# FMB-USB.net
KiCad netlist of a schematic drawn in Altium Designer
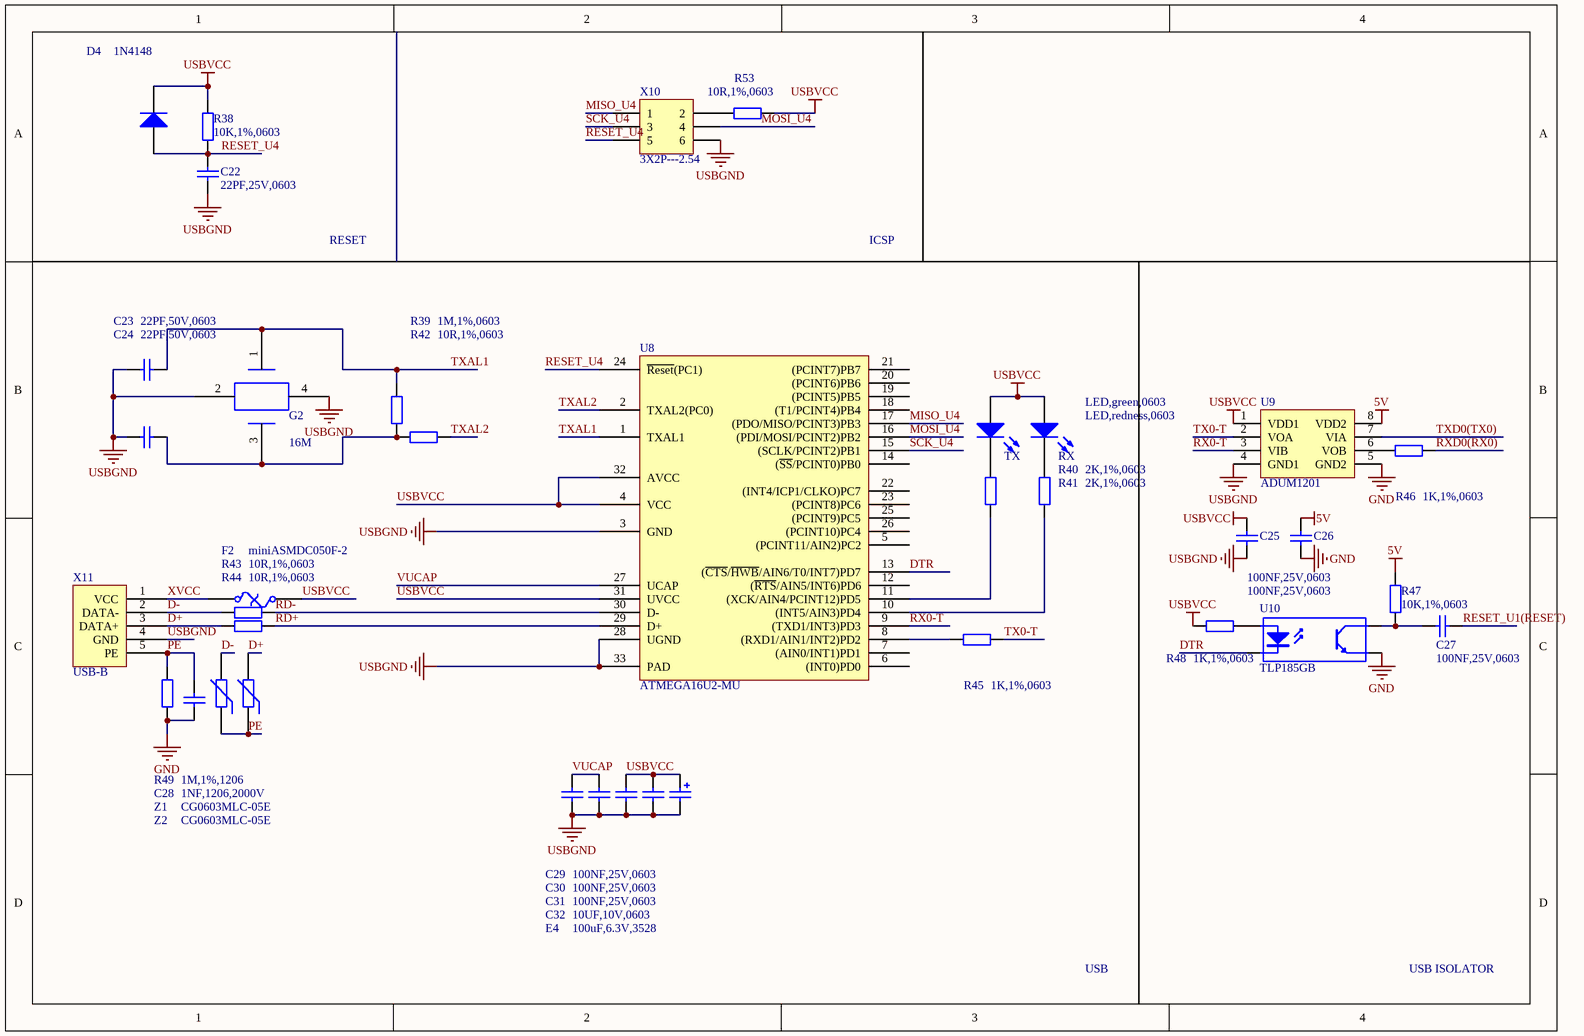
[diagram p0: FMB-USB.SchDoc]

(export (version "E")
  (design (tool "Eeschema 10.0.6"))
  (components
    (comp (ref "C22")
      (value "22PF,25V,0603")
      (footprint "RC0603")
      (description "Capacitor")
      (fields (field (name "PUBLISHER") "Altium Limited"))
      (libsource (lib "Miscellaneous Devices") (part "Cap"))
    )
    (comp (ref "C23")
      (value "22PF,50V,0603")
      (footprint "RC0603")
      (description "Capacitor")
      (fields (field (name "PUBLISHER") "Altium Limited"))
      (libsource (lib "Miscellaneous Devices") (part "Cap"))
    )
    (comp (ref "C24")
      (value "22PF,50V,0603")
      (footprint "RC0603")
      (description "Capacitor")
      (fields (field (name "PUBLISHER") "Altium Limited"))
      (libsource (lib "Miscellaneous Devices") (part "Cap"))
    )
    (comp (ref "C25")
      (value "100NF,25V,0603")
      (footprint "RC0603")
      (description "Capacitor")
      (fields (field (name "PUBLISHER") "Altium Limited"))
      (libsource (lib "Miscellaneous Devices") (part "Cap"))
    )
    (comp (ref "C26")
      (value "100NF,25V,0603")
      (footprint "RC0603")
      (description "Capacitor")
      (fields (field (name "PUBLISHER") "Altium Limited"))
      (libsource (lib "Miscellaneous Devices") (part "Cap"))
    )
    (comp (ref "C27")
      (value "100NF,25V,0603")
      (footprint "RC0603")
      (description "Capacitor")
      (fields (field (name "PUBLISHER") "Altium Limited"))
      (libsource (lib "Miscellaneous Devices") (part "Cap"))
    )
    (comp (ref "C28")
      (value "1NF,1206,2000V")
      (footprint "RC1206")
      (description "Capacitor")
      (fields (field (name "PUBLISHER") "Altium Limited"))
      (libsource (lib "Miscellaneous Devices") (part "Cap"))
    )
    (comp (ref "C29")
      (value "100NF,25V,0603")
      (footprint "RC0603")
      (description "Capacitor")
      (fields (field (name "PUBLISHER") "Altium Limited"))
      (libsource (lib "Miscellaneous Devices") (part "Cap"))
    )
    (comp (ref "C30")
      (value "100NF,25V,0603")
      (footprint "RC0603")
      (description "Capacitor")
      (fields (field (name "PUBLISHER") "Altium Limited"))
      (libsource (lib "Miscellaneous Devices") (part "Cap"))
    )
    (comp (ref "C31")
      (value "100NF,25V,0603")
      (footprint "RC0603")
      (description "Capacitor")
      (fields (field (name "PUBLISHER") "Altium Limited"))
      (libsource (lib "Miscellaneous Devices") (part "Cap"))
    )
    (comp (ref "C32")
      (value "10UF,10V,0603")
      (footprint "RC0603")
      (description "Capacitor")
      (fields (field (name "PUBLISHER") "Altium Limited"))
      (libsource (lib "Miscellaneous Devices") (part "Cap"))
    )
    (comp (ref "D4")
      (value "1N4148")
      (footprint "SOD-323")
      (description "Default Diode")
      (fields (field (name "PUBLISHER") "Altium Limited"))
      (libsource (lib "Miscellaneous Devices") (part "Diode"))
    )
    (comp (ref "E4")
      (value "100uF,6.3V,3528")
      (footprint "3528-21")
      (description "Polarized Capacitor (Axial)")
      (fields (field (name "PUBLISHER") "Altium Limited"))
      (libsource (lib "Miscellaneous Devices") (part "Cap Pol2"))
    )
    (comp (ref "F2")
      (value "miniASMDC050F-2")
      (footprint "RC1812")
      (description "Thermal Fuse")
      (fields (field (name "PUBLISHER") "Altium Limited"))
      (libsource (lib "Miscellaneous Devices") (part "Fuse Thermal"))
    )
    (comp (ref "G2") (value "16M") (footprint "Y-3225") (libsource (lib "STM32F407VE") (part "G")))
    (comp (ref "R38")
      (value "10K,1%,0603")
      (footprint "RC0603")
      (description "Resistor")
      (fields (field (name "PUBLISHER") "Altium Limited"))
      (libsource (lib "") (part "Res2_1"))
    )
    (comp (ref "R39")
      (value "1M,1%,0603")
      (footprint "RC0603")
      (description "Resistor")
      (fields (field (name "PUBLISHER") "Altium Limited"))
      (libsource (lib "") (part "Res2_1"))
    )
    (comp (ref "R40")
      (value "2K,1%,0603")
      (footprint "RC0603")
      (description "Resistor")
      (fields (field (name "PUBLISHER") "Altium Limited"))
      (libsource (lib "") (part "Res2_1"))
    )
    (comp (ref "R41")
      (value "2K,1%,0603")
      (footprint "RC0603")
      (description "Resistor")
      (fields (field (name "PUBLISHER") "Altium Limited"))
      (libsource (lib "") (part "Res2_1"))
    )
    (comp (ref "R42")
      (value "10R,1%,0603")
      (footprint "RC0603")
      (description "Resistor")
      (fields (field (name "PUBLISHER") "Altium Limited"))
      (libsource (lib "Miscellaneous Devices") (part "Res2"))
    )
    (comp (ref "R43")
      (value "10R,1%,0603")
      (footprint "RC0603")
      (description "Resistor")
      (fields (field (name "PUBLISHER") "Altium Limited"))
      (libsource (lib "Miscellaneous Devices") (part "Res2"))
    )
    (comp (ref "R44")
      (value "10R,1%,0603")
      (footprint "RC0603")
      (description "Resistor")
      (fields (field (name "PUBLISHER") "Altium Limited"))
      (libsource (lib "Miscellaneous Devices") (part "Res2"))
    )
    (comp (ref "R45")
      (value "1K,1%,0603")
      (footprint "RC0603")
      (description "Resistor")
      (fields (field (name "PUBLISHER") "Altium Limited"))
      (libsource (lib "") (part "Res2_3"))
    )
    (comp (ref "R46")
      (value "1K,1%,0603")
      (footprint "RC0603")
      (description "Resistor")
      (fields (field (name "PUBLISHER") "Altium Limited"))
      (libsource (lib "") (part "Res2_3"))
    )
    (comp (ref "R47")
      (value "10K,1%,0603")
      (footprint "RC0603")
      (description "Resistor")
      (fields (field (name "PUBLISHER") "Altium Limited"))
      (libsource (lib "") (part "Res2_2"))
    )
    (comp (ref "R48")
      (value "1K,1%,0603")
      (footprint "RC0603")
      (description "Resistor")
      (fields (field (name "PUBLISHER") "Altium Limited"))
      (libsource (lib "Miscellaneous Devices") (part "Res2"))
    )
    (comp (ref "R49")
      (value "1M,1%,1206")
      (footprint "RC1206")
      (description "Resistor")
      (fields (field (name "PUBLISHER") "Altium Limited"))
      (libsource (lib "") (part "Res2_2"))
    )
    (comp (ref "R53")
      (value "10R,1%,0603")
      (footprint "RC0603")
      (description "Resistor")
      (fields (field (name "PUBLISHER") "Altium Limited"))
      (libsource (lib "") (part "Res2_3"))
    )
    (comp (ref "RX")
      (value "LED,redness,0603")
      (footprint "LED-0603")
      (description "Typical INFRARED GaAs LED")
      (fields (field (name "PUBLISHER") "Altium Limited"))
      (libsource (lib "Miscellaneous Devices") (part "LED0"))
    )
    (comp (ref "TX")
      (value "LED,green,0603")
      (footprint "LED-0603")
      (description "Typical INFRARED GaAs LED")
      (fields (field (name "PUBLISHER") "Altium Limited"))
      (libsource (lib "Miscellaneous Devices") (part "LED0"))
    )
    (comp (ref "U8")
      (value "ATMEGA16U2-MU")
      (footprint "QFN-32")
      (libsource (lib "LDO原理图库") (part "ATMEGA8U2-MU"))
    )
    (comp (ref "U9") (value "ADUM1201") (footprint "SO-8N") (libsource (lib "ADUM1201") (part "ADUM1201")))
    (comp (ref "U10")
      (value "TLP185GB")
      (footprint "SO-4")
      (description "4-Pin Phototransistor Optocoupler")
      (fields (field (name "PUBLISHER") "Altium Limited"))
      (libsource (lib "Miscellaneous Devices") (part "Optoisolator1"))
    )
    (comp (ref "X10")
      (value "3X2P---2.54")
      (footprint "HDR2X3")
      (description "Header, 3-Pin, Dual row")
      (fields (field (name "PUBLISHER") "Altium Limited"))
      (libsource (lib "Miscellaneous Connectors") (part "Header 3X2"))
    )
    (comp (ref "X11") (value "USB-B") (footprint "USB-B180") (libsource (lib "LDO原理图库") (part "B-USC")))
    (comp (ref "Z1")
      (value "CG0603MLC-05E")
      (footprint "RC0603")
      (description "Varistor (Voltage-Sensitive Resistor)")
      (fields (field (name "PUBLISHER") "Altium Limited"))
      (libsource (lib "Miscellaneous Devices") (part "Res Varistor"))
    )
    (comp (ref "Z2")
      (value "CG0603MLC-05E")
      (footprint "RC0603")
      (description "Varistor (Voltage-Sensitive Resistor)")
      (fields (field (name "PUBLISHER") "Altium Limited"))
      (libsource (lib "Miscellaneous Devices") (part "Res Varistor"))
    )
  )
  (nets
    (net (code "1") (name "/D+") (class "Default")
      (node (ref "R44") (pin "1") (pinfunction "1_1") (pintype "passive"))
      (node (ref "X11") (pin "3") (pinfunction "DATA+_3") (pintype "passive"))
      (node (ref "Z2") (pin "2") (pinfunction "2_2") (pintype "passive"))
    )
    (net (code "2") (name "/D-") (class "Default")
      (node (ref "R43") (pin "1") (pinfunction "1_1") (pintype "passive"))
      (node (ref "X11") (pin "2") (pinfunction "DATA-_2") (pintype "passive"))
      (node (ref "Z1") (pin "2") (pinfunction "2_2") (pintype "passive"))
    )
    (net (code "3") (name "/DTR") (class "Default")
      (node (ref "U10") (pin "2") (pinfunction "K_2") (pintype "passive"))
      (node (ref "U8") (pin "13") (pinfunction "(~{CTS}/~{HWB}/AIN6/T0/INT7)PD7_13") (pintype "passive"))
    )
    (net (code "4") (name "/MISO_U4") (class "Default")
      (node (ref "U8") (pin "17") (pinfunction "(PDO/MISO/PCINT3)PB3_17") (pintype "passive"))
      (node (ref "X10") (pin "1") (pinfunction "1_1") (pintype "passive"))
    )
    (net (code "5") (name "/MOSI_U4") (class "Default")
      (node (ref "U8") (pin "16") (pinfunction "(PDI/MOSI/PCINT2)PB2_16") (pintype "passive"))
      (node (ref "X10") (pin "4") (pinfunction "4_4") (pintype "passive"))
    )
    (net (code "6") (name "/PE") (class "Default")
      (node (ref "C28") (pin "2") (pinfunction "2_2") (pintype "passive"))
      (node (ref "R49") (pin "2") (pinfunction "2_2") (pintype "passive"))
      (node (ref "X11") (pin "5") (pinfunction "PE_5") (pintype "passive"))
      (node (ref "Z1") (pin "1") (pinfunction "1_1") (pintype "passive"))
      (node (ref "Z2") (pin "1") (pinfunction "1_1") (pintype "passive"))
    )
    (net (code "7") (name "/RD+") (class "Default")
      (node (ref "R44") (pin "2") (pinfunction "2_2") (pintype "passive"))
      (node (ref "U8") (pin "29") (pinfunction "D+_29") (pintype "passive"))
    )
    (net (code "8") (name "/RD-") (class "Default")
      (node (ref "R43") (pin "2") (pinfunction "2_2") (pintype "passive"))
      (node (ref "U8") (pin "30") (pinfunction "D-_30") (pintype "passive"))
    )
    (net (code "9") (name "/RESET_U1(RESET)") (class "Default")
      (node (ref "C27") (pin "1") (pinfunction "1_1") (pintype "passive"))
    )
    (net (code "10") (name "/RESET_U4") (class "Default")
      (node (ref "C22") (pin "1") (pinfunction "1_1") (pintype "passive"))
      (node (ref "D4") (pin "1") (pinfunction "A_1") (pintype "passive"))
      (node (ref "R38") (pin "2") (pinfunction "2_2") (pintype "passive"))
      (node (ref "U8") (pin "24") (pinfunction "~{Reset}(PC1)_24") (pintype "passive"))
      (node (ref "X10") (pin "5") (pinfunction "5_5") (pintype "passive"))
    )
    (net (code "11") (name "/RX0-T") (class "Default")
      (node (ref "U8") (pin "9") (pinfunction "(TXD1/INT3)PD3_9") (pintype "passive"))
      (node (ref "U9") (pin "3") (pinfunction "VIB_3") (pintype "passive"))
    )
    (net (code "12") (name "/RXD0(RX0)") (class "Default")
      (node (ref "R46") (pin "1") (pinfunction "1_1") (pintype "passive"))
    )
    (net (code "13") (name "/SCK_U4") (class "Default")
      (node (ref "U8") (pin "15") (pinfunction "(SCLK/PCINT2)PB1_15") (pintype "passive"))
      (node (ref "X10") (pin "3") (pinfunction "3_3") (pintype "passive"))
    )
    (net (code "14") (name "/TX0-T") (class "Default")
      (node (ref "R45") (pin "1") (pinfunction "1_1") (pintype "passive"))
      (node (ref "U9") (pin "2") (pinfunction "VOA_2") (pintype "passive"))
    )
    (net (code "15") (name "/TXAL1") (class "Default")
      (node (ref "C23") (pin "1") (pinfunction "1_1") (pintype "passive"))
      (node (ref "G2") (pin "1") (pintype "passive"))
      (node (ref "R39") (pin "1") (pinfunction "1_1") (pintype "passive"))
      (node (ref "U8") (pin "1") (pinfunction "TXAL1_1") (pintype "passive"))
    )
    (net (code "16") (name "/TXAL2") (class "Default")
      (node (ref "R42") (pin "2") (pinfunction "2_2") (pintype "passive"))
      (node (ref "U8") (pin "2") (pinfunction "TXAL2(PC0)_2") (pintype "passive"))
    )
    (net (code "17") (name "/TXD0(TX0)") (class "Default")
      (node (ref "U9") (pin "7") (pinfunction "VIA_7") (pintype "passive"))
    )
    (net (code "18") (name "/VUCAP") (class "Default")
      (node (ref "C29") (pin "2") (pinfunction "2_2") (pintype "passive"))
      (node (ref "C30") (pin "2") (pinfunction "2_2") (pintype "passive"))
      (node (ref "U8") (pin "27") (pinfunction "UCAP_27") (pintype "passive"))
    )
    (net (code "19") (name "/XVCC") (class "Default")
      (node (ref "F2") (pin "1") (pinfunction "1_1") (pintype "passive"))
      (node (ref "X11") (pin "1") (pinfunction "VCC_1") (pintype "passive"))
    )
    (net (code "20") (name "5V") (class "Default")
      (node (ref "C26") (pin "1") (pinfunction "1_1") (pintype "passive"))
      (node (ref "R47") (pin "2") (pinfunction "2_2") (pintype "passive"))
      (node (ref "U9") (pin "8") (pinfunction "VDD2_8") (pintype "passive"))
    )
    (net (code "21") (name "GND") (class "Default")
      (node (ref "C26") (pin "2") (pinfunction "2_2") (pintype "passive"))
      (node (ref "C28") (pin "1") (pinfunction "1_1") (pintype "passive"))
      (node (ref "R49") (pin "1") (pinfunction "1_1") (pintype "passive"))
      (node (ref "U10") (pin "3") (pinfunction "E_3") (pintype "passive"))
      (node (ref "U9") (pin "5") (pinfunction "GND2_5") (pintype "passive"))
    )
    (net (code "22") (name "Net-(C24-Pad1)") (class "Default")
      (node (ref "C24") (pin "1") (pinfunction "1_1") (pintype "passive"))
      (node (ref "G2") (pin "3") (pintype "passive"))
      (node (ref "R39") (pin "2") (pinfunction "2_2") (pintype "passive"))
      (node (ref "R42") (pin "1") (pinfunction "1_1") (pintype "passive"))
    )
    (net (code "23") (name "Net-(R53-Pad2)") (class "Default")
      (node (ref "R53") (pin "2") (pinfunction "2_2") (pintype "passive"))
      (node (ref "X10") (pin "2") (pinfunction "2_2") (pintype "passive"))
    )
    (net (code "24") (name "Net-(RX-K)") (class "Default")
      (node (ref "R41") (pin "1") (pinfunction "1_1") (pintype "passive"))
      (node (ref "RX") (pin "2") (pinfunction "K_2") (pintype "passive"))
    )
    (net (code "25") (name "Net-(TX-K)") (class "Default")
      (node (ref "R40") (pin "1") (pinfunction "1_1") (pintype "passive"))
      (node (ref "TX") (pin "2") (pinfunction "K_2") (pintype "passive"))
    )
    (net (code "26") (name "Net-(U8-(INT5{slash}AIN3)PD4)") (class "Default")
      (node (ref "R41") (pin "2") (pinfunction "2_2") (pintype "passive"))
      (node (ref "U8") (pin "10") (pinfunction "(INT5/AIN3)PD4_10") (pintype "passive"))
    )
    (net (code "27") (name "Net-(U8-(RXD1{slash}AIN1{slash}INT2)PD2)") (class "Default")
      (node (ref "R45") (pin "2") (pinfunction "2_2") (pintype "passive"))
      (node (ref "U8") (pin "8") (pinfunction "(RXD1/AIN1/INT2)PD2_8") (pintype "passive"))
    )
    (net (code "28") (name "Net-(U8-(XCK{slash}AIN4{slash}PCINT12)PD5)") (class "Default")
      (node (ref "R40") (pin "2") (pinfunction "2_2") (pintype "passive"))
      (node (ref "U8") (pin "11") (pinfunction "(XCK/AIN4/PCINT12)PD5_11") (pintype "passive"))
    )
    (net (code "29") (name "Net-(U9-VOB)") (class "Default")
      (node (ref "R46") (pin "2") (pinfunction "2_2") (pintype "passive"))
      (node (ref "U9") (pin "6") (pinfunction "VOB_6") (pintype "passive"))
    )
    (net (code "30") (name "Net-(U10-A)") (class "Default")
      (node (ref "R48") (pin "2") (pinfunction "2_2") (pintype "passive"))
      (node (ref "U10") (pin "1") (pinfunction "A_1") (pintype "passive"))
    )
    (net (code "31") (name "Net-(U10-C)") (class "Default")
      (node (ref "C27") (pin "2") (pinfunction "2_2") (pintype "passive"))
      (node (ref "R47") (pin "1") (pinfunction "1_1") (pintype "passive"))
      (node (ref "U10") (pin "4") (pinfunction "C_4") (pintype "passive"))
    )
    (net (code "32") (name "USBGND") (class "Default")
      (node (ref "C22") (pin "2") (pinfunction "2_2") (pintype "passive"))
      (node (ref "C23") (pin "2") (pinfunction "2_2") (pintype "passive"))
      (node (ref "C24") (pin "2") (pinfunction "2_2") (pintype "passive"))
      (node (ref "C25") (pin "1") (pinfunction "1_1") (pintype "passive"))
      (node (ref "C29") (pin "1") (pinfunction "1_1") (pintype "passive"))
      (node (ref "C30") (pin "1") (pinfunction "1_1") (pintype "passive"))
      (node (ref "C31") (pin "1") (pinfunction "1_1") (pintype "passive"))
      (node (ref "C32") (pin "1") (pinfunction "1_1") (pintype "passive"))
      (node (ref "E4") (pin "2") (pinfunction "2_2") (pintype "passive"))
      (node (ref "G2") (pin "2") (pintype "passive"))
      (node (ref "G2") (pin "4") (pintype "passive"))
      (node (ref "U8") (pin "28") (pinfunction "UGND_28") (pintype "passive"))
      (node (ref "U8") (pin "3") (pinfunction "GND_3") (pintype "passive"))
      (node (ref "U8") (pin "33") (pinfunction "PAD_33") (pintype "passive"))
      (node (ref "U9") (pin "4") (pinfunction "GND1_4") (pintype "passive"))
      (node (ref "X10") (pin "6") (pinfunction "6_6") (pintype "passive"))
      (node (ref "X11") (pin "4") (pinfunction "GND_4") (pintype "passive"))
    )
    (net (code "33") (name "USBVCC") (class "Default")
      (node (ref "C25") (pin "2") (pinfunction "2_2") (pintype "passive"))
      (node (ref "C31") (pin "2") (pinfunction "2_2") (pintype "passive"))
      (node (ref "C32") (pin "2") (pinfunction "2_2") (pintype "passive"))
      (node (ref "D4") (pin "2") (pinfunction "K_2") (pintype "passive"))
      (node (ref "E4") (pin "1") (pinfunction "1_1") (pintype "passive"))
      (node (ref "F2") (pin "2") (pinfunction "2_2") (pintype "passive"))
      (node (ref "R38") (pin "1") (pinfunction "1_1") (pintype "passive"))
      (node (ref "R48") (pin "1") (pinfunction "1_1") (pintype "passive"))
      (node (ref "R53") (pin "1") (pinfunction "1_1") (pintype "passive"))
      (node (ref "RX") (pin "1") (pinfunction "A_1") (pintype "passive"))
      (node (ref "TX") (pin "1") (pinfunction "A_1") (pintype "passive"))
      (node (ref "U8") (pin "31") (pinfunction "UVCC_31") (pintype "passive"))
      (node (ref "U8") (pin "32") (pinfunction "AVCC_32") (pintype "passive"))
      (node (ref "U8") (pin "4") (pinfunction "VCC_4") (pintype "passive"))
      (node (ref "U9") (pin "1") (pinfunction "VDD1_1") (pintype "passive"))
    )
    (net (code "34") (name "unconnected-(U8-(AIN0{slash}INT1)PD1-Pad7)") (class "Default")
      (node (ref "U8") (pin "7") (pinfunction "(AIN0/INT1)PD1_7") (pintype "passive"))
    )
    (net (code "35") (name "unconnected-(U8-(INT0)PD0-Pad6)") (class "Default")
      (node (ref "U8") (pin "6") (pinfunction "(INT0)PD0_6") (pintype "passive"))
    )
    (net (code "36") (name "unconnected-(U8-(INT4{slash}ICP1{slash}CLKO)PC7-Pad22)") (class "Default")
      (node (ref "U8") (pin "22") (pinfunction "(INT4/ICP1/CLKO)PC7_22") (pintype "passive"))
    )
    (net (code "37") (name "unconnected-(U8-(PCINT5)PB5-Pad19)") (class "Default")
      (node (ref "U8") (pin "19") (pinfunction "(PCINT5)PB5_19") (pintype "passive"))
    )
    (net (code "38") (name "unconnected-(U8-(PCINT6)PB6-Pad20)") (class "Default")
      (node (ref "U8") (pin "20") (pinfunction "(PCINT6)PB6_20") (pintype "passive"))
    )
    (net (code "39") (name "unconnected-(U8-(PCINT7)PB7-Pad21)") (class "Default")
      (node (ref "U8") (pin "21") (pinfunction "(PCINT7)PB7_21") (pintype "passive"))
    )
    (net (code "40") (name "unconnected-(U8-(PCINT8)PC6-Pad23)") (class "Default")
      (node (ref "U8") (pin "23") (pinfunction "(PCINT8)PC6_23") (pintype "passive"))
    )
    (net (code "41") (name "unconnected-(U8-(PCINT9)PC5-Pad25)") (class "Default")
      (node (ref "U8") (pin "25") (pinfunction "(PCINT9)PC5_25") (pintype "passive"))
    )
    (net (code "42") (name "unconnected-(U8-(PCINT10)PC4-Pad26)") (class "Default")
      (node (ref "U8") (pin "26") (pinfunction "(PCINT10)PC4_26") (pintype "passive"))
    )
    (net (code "43") (name "unconnected-(U8-(PCINT11{slash}AIN2)PC2-Pad5)") (class "Default")
      (node (ref "U8") (pin "5") (pinfunction "(PCINT11/AIN2)PC2_5") (pintype "passive"))
    )
    (net (code "44") (name "unconnected-(U8-(T1{slash}PCINT4)PB4-Pad18)") (class "Default")
      (node (ref "U8") (pin "18") (pinfunction "(T1/PCINT4)PB4_18") (pintype "passive"))
    )
    (net (code "45") (name "unconnected-(U8-(~{RTS}{slash}AIN5{slash}INT6)PD6-Pad12)") (class "Default")
      (node (ref "U8") (pin "12") (pinfunction "(~{RTS}/AIN5/INT6)PD6_12") (pintype "passive"))
    )
    (net (code "46") (name "unconnected-(U8-(~{SS}{slash}PCINT0)PB0-Pad14)") (class "Default")
      (node (ref "U8") (pin "14") (pinfunction "(~{SS}/PCINT0)PB0_14") (pintype "passive"))
    )
  )
)
